# BusPirate-v4_ecard.net
KiCad netlist of a schematic drawn in EAGLE
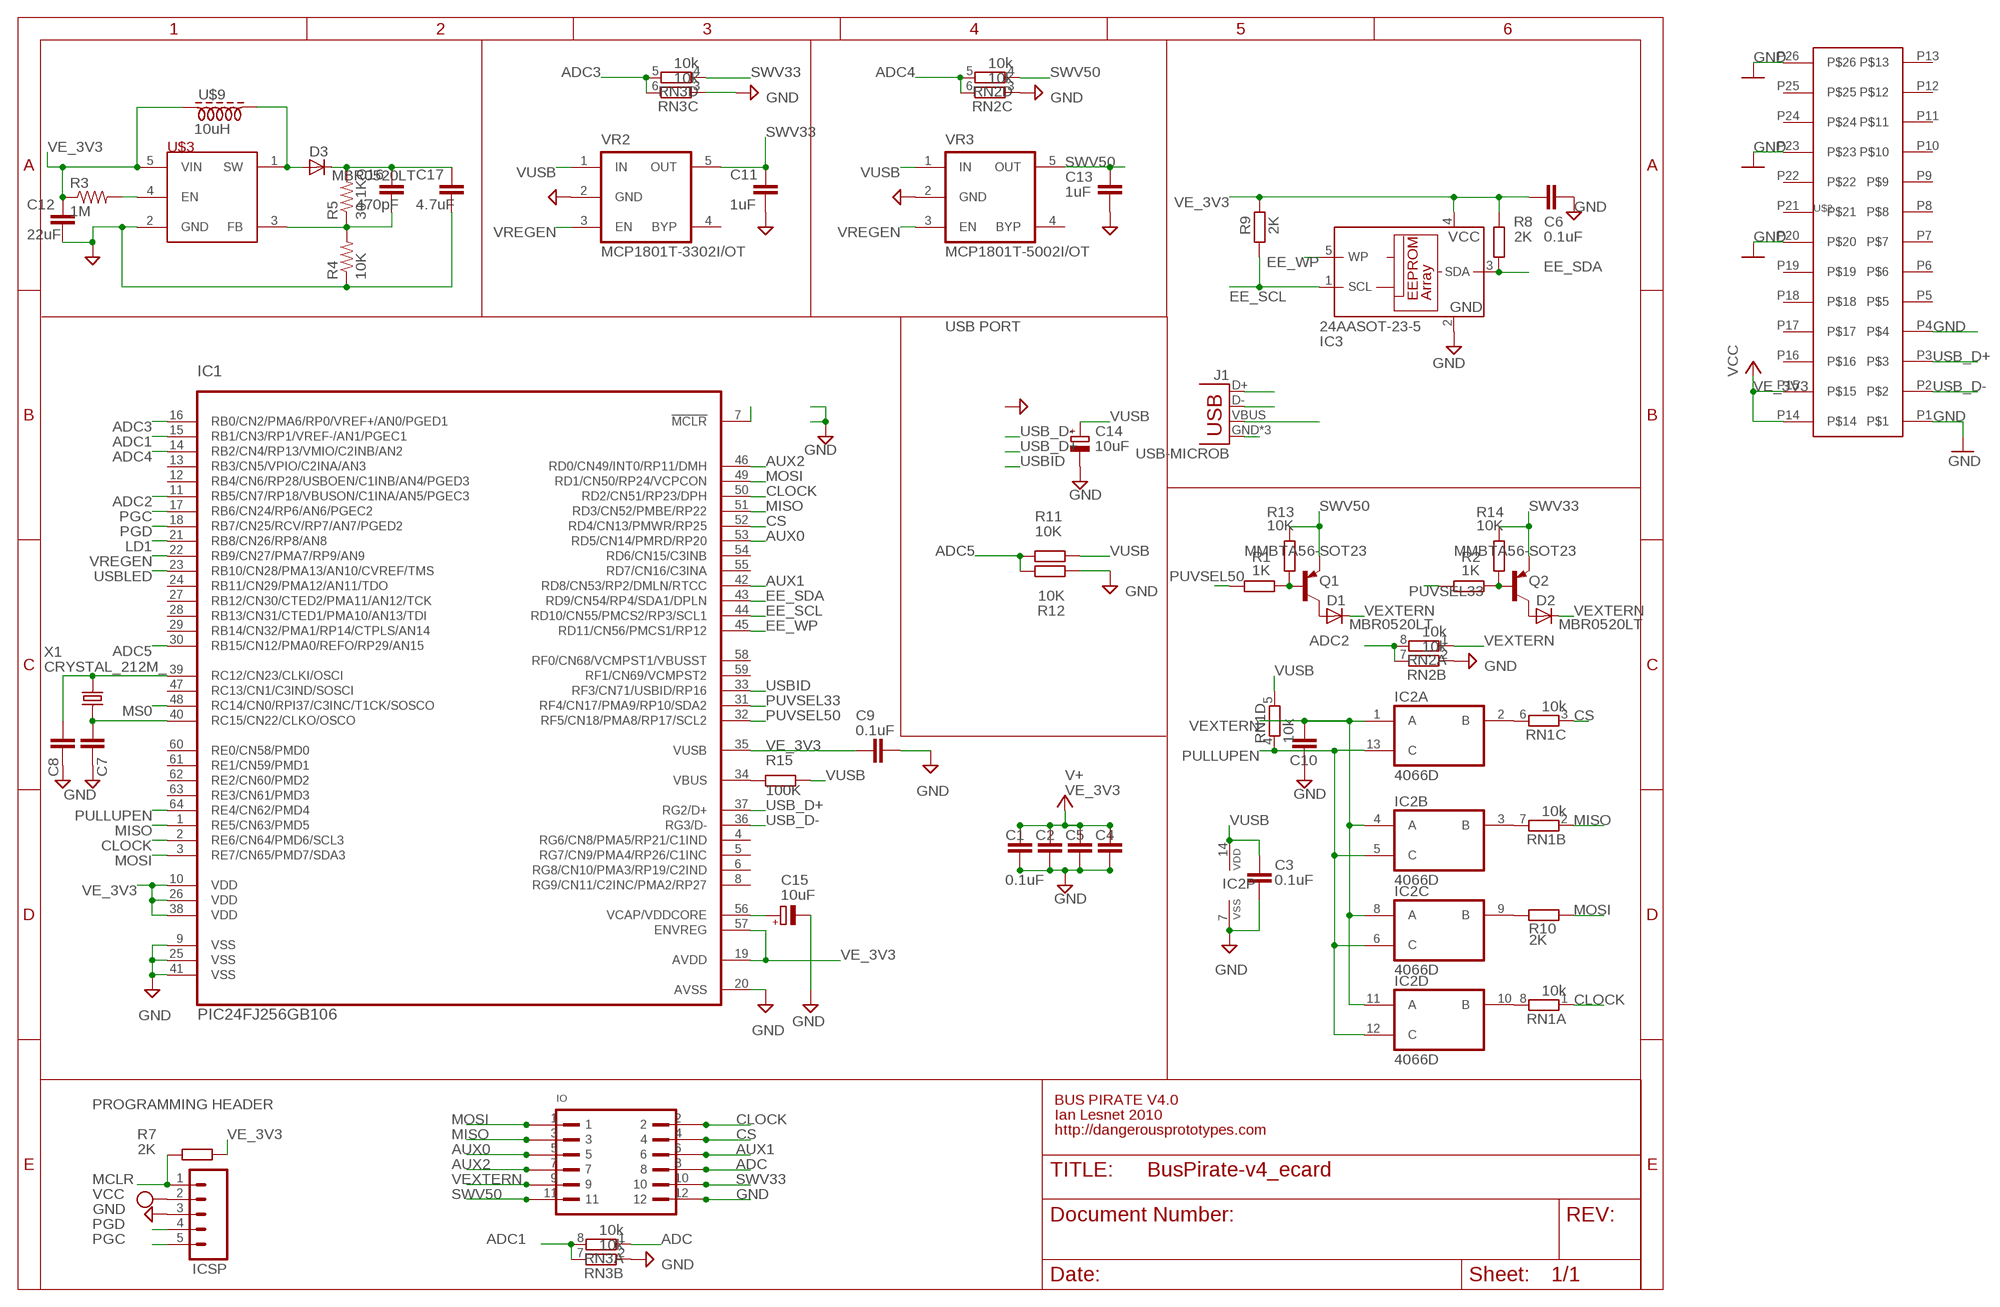
[diagram p0: schematic, sheet 1]

(export (version "E")
  (design (tool "Eeschema 10.0.6"))
  (components
    (comp (ref "C1")
      (value "0.1uF")
      (footprint "eagle-import:C0603")
      (libsource (lib "eagle-import") (part "C-EUC0603"))
    )
    (comp (ref "C2")
      (value "0.1uF")
      (footprint "eagle-import:C0603")
      (libsource (lib "eagle-import") (part "C-EUC0603"))
    )
    (comp (ref "C3")
      (value "0.1uF")
      (footprint "eagle-import:C0603")
      (libsource (lib "eagle-import") (part "C-EUC0603"))
    )
    (comp (ref "C4")
      (value "0.1uF")
      (footprint "eagle-import:C0603")
      (libsource (lib "eagle-import") (part "C-EUC0603"))
    )
    (comp (ref "C5")
      (value "0.1uF")
      (footprint "eagle-import:C0603")
      (libsource (lib "eagle-import") (part "C-EUC0603"))
    )
    (comp (ref "C6")
      (value "0.1uF")
      (footprint "eagle-import:C0603")
      (libsource (lib "eagle-import") (part "C-EUC0603"))
    )
    (comp (ref "C7")
      (value "27pF")
      (footprint "eagle-import:C0603")
      (libsource (lib "eagle-import") (part "C-EUC0603"))
    )
    (comp (ref "C8")
      (value "27pF")
      (footprint "eagle-import:C0603")
      (libsource (lib "eagle-import") (part "C-EUC0603"))
    )
    (comp (ref "C9")
      (value "0.1uF")
      (footprint "eagle-import:C0603")
      (libsource (lib "eagle-import") (part "C-EUC0603"))
    )
    (comp (ref "C10")
      (value "0.1uF")
      (footprint "eagle-import:C0603")
      (libsource (lib "eagle-import") (part "C-EUC0603"))
    )
    (comp (ref "C11")
      (value "1uF")
      (footprint "eagle-import:C0603")
      (libsource (lib "eagle-import") (part "C-EUC0603"))
    )
    (comp (ref "C12")
      (value "22uF")
      (footprint "eagle-import:C0603")
      (libsource (lib "eagle-import") (part "C-EUC0603"))
    )
    (comp (ref "C13")
      (value "1uF")
      (footprint "eagle-import:C0603")
      (libsource (lib "eagle-import") (part "C-EUC0603"))
    )
    (comp (ref "C14")
      (value "10uF")
      (footprint "eagle-import:SMC_A")
      (libsource (lib "eagle-import") (part "CPOL-EUSMCA"))
    )
    (comp (ref "C15")
      (value "10uF")
      (footprint "eagle-import:SMC_A")
      (libsource (lib "eagle-import") (part "CPOL-EUSMCA"))
    )
    (comp (ref "C16")
      (value "470pF")
      (footprint "eagle-import:C0603")
      (libsource (lib "eagle-import") (part "C-EUC0603"))
    )
    (comp (ref "C17")
      (value "4.7uF")
      (footprint "eagle-import:C0603")
      (libsource (lib "eagle-import") (part "C-EUC0603"))
    )
    (comp (ref "D1")
      (value "MBR0520LT")
      (footprint "eagle-import:SOD123")
      (libsource (lib "eagle-import") (part "MBR0520LT"))
    )
    (comp (ref "D2")
      (value "MBR0520LT")
      (footprint "eagle-import:SOD123")
      (libsource (lib "eagle-import") (part "MBR0520LT"))
    )
    (comp (ref "D3")
      (value "MBR0520LT")
      (footprint "eagle-import:SOD123")
      (libsource (lib "eagle-import") (part "MBR0520LT"))
    )
    (comp (ref "IC1")
      (value "PIC24FJ256GB106")
      (footprint "eagle-import:TQFP64-10X10")
      (libsource (lib "eagle-import") (part "PIC24FJ256GB106"))
    )
    (comp (ref "IC2")
      (value "4066D")
      (footprint "eagle-import:SO14")
      (libsource (lib "eagle-import") (part "4066D"))
    )
    (comp (ref "IC3")
      (value "24AASOT-23-5")
      (footprint "eagle-import:SOT-23-5")
      (libsource (lib "eagle-import") (part "24AA"))
    )
    (comp (ref "ICSP")
      (value "ICSP")
      (footprint "eagle-import:1X05")
      (libsource (lib "eagle-import") (part "M05"))
    )
    (comp (ref "IO")
      (value "PINSHRD-PTH-2X06")
      (footprint "eagle-import:PINSHRD_PTH_2X06")
      (libsource (lib "eagle-import") (part "PINSHRD-PTH-2X06"))
    )
    (comp (ref "J1")
      (value "USB-MICROB")
      (footprint "eagle-import:USB-MICROB")
      (libsource (lib "eagle-import") (part "USB-MICROB"))
    )
    (comp (ref "Q1")
      (value "MMBTA56-SOT23")
      (footprint "eagle-import:SOT23")
      (libsource (lib "eagle-import") (part "-?SOT23MMBTA56"))
    )
    (comp (ref "Q2")
      (value "MMBTA56-SOT23")
      (footprint "eagle-import:SOT23")
      (libsource (lib "eagle-import") (part "-?SOT23MMBTA56"))
    )
    (comp (ref "R1")
      (value "1K")
      (footprint "eagle-import:R0603")
      (libsource (lib "eagle-import") (part "R-EU_R0603"))
    )
    (comp (ref "R2")
      (value "1K")
      (footprint "eagle-import:R0603")
      (libsource (lib "eagle-import") (part "R-EU_R0603"))
    )
    (comp (ref "R3")
      (value "1M")
      (footprint "eagle-import:R0603")
      (libsource (lib "eagle-import") (part "R-US_R0603"))
    )
    (comp (ref "R4")
      (value "10K")
      (footprint "eagle-import:R0603")
      (libsource (lib "eagle-import") (part "R-US_R0603"))
    )
    (comp (ref "R5")
      (value "30.1K")
      (footprint "eagle-import:R0603")
      (libsource (lib "eagle-import") (part "R-US_R0603"))
    )
    (comp (ref "R7")
      (value "2K")
      (footprint "eagle-import:R0603")
      (libsource (lib "eagle-import") (part "R-EU_R0603"))
    )
    (comp (ref "R8")
      (value "2K")
      (footprint "eagle-import:R0603")
      (libsource (lib "eagle-import") (part "R-EU_R0603"))
    )
    (comp (ref "R9")
      (value "2K")
      (footprint "eagle-import:R0603")
      (libsource (lib "eagle-import") (part "R-EU_R0603"))
    )
    (comp (ref "R10")
      (value "2K")
      (footprint "eagle-import:R0603")
      (libsource (lib "eagle-import") (part "R-EU_R0603"))
    )
    (comp (ref "R11")
      (value "10K")
      (footprint "eagle-import:R0603")
      (libsource (lib "eagle-import") (part "resistor_R-EU_R0603"))
    )
    (comp (ref "R12")
      (value "10K")
      (footprint "eagle-import:R0603")
      (libsource (lib "eagle-import") (part "resistor_R-EU_R0603"))
    )
    (comp (ref "R13")
      (value "10K")
      (footprint "eagle-import:R0603")
      (libsource (lib "eagle-import") (part "R-EU_R0603"))
    )
    (comp (ref "R14")
      (value "10K")
      (footprint "eagle-import:R0603")
      (libsource (lib "eagle-import") (part "R-EU_R0603"))
    )
    (comp (ref "R15")
      (value "100K")
      (footprint "eagle-import:R0603")
      (libsource (lib "eagle-import") (part "R-EU_R0603"))
    )
    (comp (ref "RN1")
      (value "10k")
      (footprint "eagle-import:RN8P-4R-CRA06S")
      (libsource (lib "eagle-import") (part "RNETWORK"))
    )
    (comp (ref "RN2")
      (value "10k")
      (footprint "eagle-import:RN8P-4R-CRA06S")
      (libsource (lib "eagle-import") (part "RNETWORK"))
    )
    (comp (ref "RN3")
      (value "10k")
      (footprint "eagle-import:RN8P-4R-CRA06S")
      (libsource (lib "eagle-import") (part "RNETWORK"))
    )
    (comp (ref "U$2")
      (value "EXPRESSCARD")
      (footprint "eagle-import:EXPRESSCARD_EXPRESSCARD_PACK")
      (libsource (lib "eagle-import") (part "EXPRESSCARD"))
    )
    (comp (ref "U$3")
      (value "LMR62421")
      (footprint "eagle-import:SOT23-DBV")
      (libsource (lib "eagle-import") (part "LMR62421"))
    )
    (comp (ref "U$9")
      (value "10uH")
      (footprint "eagle-import:2520(1008)")
      (libsource (lib "eagle-import") (part "SMD_IND"))
    )
    (comp (ref "VR2")
      (value "MCP1801T-3302I/OT")
      (footprint "eagle-import:SOT-23-5")
      (libsource (lib "eagle-import") (part "MIC5205"))
    )
    (comp (ref "VR3")
      (value "MCP1801T-5002I/OT")
      (footprint "eagle-import:SOT-23-5")
      (libsource (lib "eagle-import") (part "MIC5205"))
    )
    (comp (ref "X1")
      (value "CRYSTAL_212M_")
      (footprint "eagle-import:4X6")
      (libsource (lib "eagle-import") (part "CRYSTAL_212M_"))
    )
  )
  (nets
    (net (code "1") (name "/ADC") (class "Default")
      (node (ref "IO") (pin "8") (pinfunction "8_8") (pintype "passive"))
      (node (ref "RN3") (pin "1") (pinfunction "1_1") (pintype "passive"))
    )
    (net (code "2") (name "/ADC1") (class "Default")
      (node (ref "IC1") (pin "15") (pinfunction "RB1/CN3/RP1/VREF-/AN1/PGEC1_15") (pintype "bidirectional"))
      (node (ref "RN3") (pin "7") (pinfunction "2_7") (pintype "passive"))
      (node (ref "RN3") (pin "8") (pinfunction "2_8") (pintype "passive"))
    )
    (net (code "3") (name "/ADC2") (class "Default")
      (node (ref "IC1") (pin "11") (pinfunction "RB5/CN7/RP18/VBUSON/C1INA/AN5/PGEC3_11") (pintype "bidirectional"))
      (node (ref "RN2") (pin "7") (pinfunction "2_7") (pintype "passive"))
      (node (ref "RN2") (pin "8") (pinfunction "2_8") (pintype "passive"))
    )
    (net (code "4") (name "/ADC3") (class "Default")
      (node (ref "IC1") (pin "16") (pinfunction "RB0/CN2/PMA6/RP0/VREF+/AN0/PGED1_16") (pintype "bidirectional"))
      (node (ref "RN3") (pin "5") (pinfunction "2_5") (pintype "passive"))
      (node (ref "RN3") (pin "6") (pinfunction "2_6") (pintype "passive"))
    )
    (net (code "5") (name "/ADC4") (class "Default")
      (node (ref "IC1") (pin "14") (pinfunction "RB2/CN4/RP13/VMIO/C2INB/AN2_14") (pintype "bidirectional"))
      (node (ref "RN2") (pin "5") (pinfunction "2_5") (pintype "passive"))
      (node (ref "RN2") (pin "6") (pinfunction "2_6") (pintype "passive"))
    )
    (net (code "6") (name "/ADC5") (class "Default")
      (node (ref "IC1") (pin "30") (pinfunction "RB15/CN12/PMA0/REFO/RP29/AN15_30") (pintype "bidirectional"))
      (node (ref "R11") (pin "2") (pinfunction "2_2") (pintype "passive"))
      (node (ref "R12") (pin "2") (pinfunction "2_2") (pintype "passive"))
    )
    (net (code "7") (name "/AUX0") (class "Default")
      (node (ref "IC1") (pin "53") (pinfunction "RD5/CN14/PMRD/RP20_53") (pintype "bidirectional"))
      (node (ref "IO") (pin "5") (pinfunction "5_5") (pintype "passive"))
    )
    (net (code "8") (name "/AUX1") (class "Default")
      (node (ref "IC1") (pin "42") (pinfunction "RD8/CN53/RP2/DMLN/RTCC_42") (pintype "bidirectional"))
      (node (ref "IO") (pin "6") (pinfunction "6_6") (pintype "passive"))
    )
    (net (code "9") (name "/AUX2") (class "Default")
      (node (ref "IC1") (pin "46") (pinfunction "RD0/CN49/INT0/RP11/DMH_46") (pintype "bidirectional"))
      (node (ref "IO") (pin "7") (pinfunction "7_7") (pintype "passive"))
    )
    (net (code "10") (name "/CLOCK") (class "Default")
      (node (ref "IC1") (pin "2") (pinfunction "RE6/CN64/PMD6/SCL3_2") (pintype "bidirectional"))
      (node (ref "IC1") (pin "50") (pinfunction "RD2/CN51/RP23/DPH_50") (pintype "bidirectional"))
      (node (ref "IO") (pin "2") (pinfunction "2_2") (pintype "passive"))
      (node (ref "RN1") (pin "1") (pinfunction "1_1") (pintype "passive"))
    )
    (net (code "11") (name "/CS") (class "Default")
      (node (ref "IC1") (pin "52") (pinfunction "RD4/CN13/PMWR/RP25_52") (pintype "bidirectional"))
      (node (ref "IO") (pin "4") (pinfunction "4_4") (pintype "passive"))
      (node (ref "RN1") (pin "3") (pinfunction "1_3") (pintype "passive"))
    )
    (net (code "12") (name "/EE_SCL") (class "Default")
      (node (ref "IC1") (pin "44") (pinfunction "RD10/CN55/PMCS2/RP3/SCL1_44") (pintype "bidirectional"))
      (node (ref "IC3") (pin "1") (pinfunction "SCL_1") (pintype "input"))
      (node (ref "R9") (pin "1") (pinfunction "1_1") (pintype "passive"))
    )
    (net (code "13") (name "/EE_SDA") (class "Default")
      (node (ref "IC1") (pin "43") (pinfunction "RD9/CN54/RP4/SDA1/DPLN_43") (pintype "bidirectional"))
      (node (ref "IC3") (pin "3") (pinfunction "SDA_3") (pintype "bidirectional"))
      (node (ref "R8") (pin "1") (pinfunction "1_1") (pintype "passive"))
    )
    (net (code "14") (name "/EE_WP") (class "Default")
      (node (ref "IC1") (pin "45") (pinfunction "RD11/CN56/PMCS1/RP12_45") (pintype "bidirectional"))
      (node (ref "IC3") (pin "5") (pinfunction "WP_5") (pintype "input"))
    )
    (net (code "15") (name "/LD1") (class "Default")
      (node (ref "IC1") (pin "21") (pinfunction "RB8/CN26/RP8/AN8_21") (pintype "bidirectional"))
    )
    (net (code "16") (name "/MCLR") (class "Default")
      (node (ref "IC1") (pin "7") (pinfunction "~{MCLR}_7") (pintype "input"))
      (node (ref "ICSP") (pin "1") (pinfunction "1_1") (pintype "passive"))
      (node (ref "R7") (pin "1") (pinfunction "1_1") (pintype "passive"))
    )
    (net (code "17") (name "/MISO") (class "Default")
      (node (ref "IC1") (pin "1") (pinfunction "RE5/CN63/PMD5_1") (pintype "bidirectional"))
      (node (ref "IC1") (pin "51") (pinfunction "RD3/CN52/PMBE/RP22_51") (pintype "bidirectional"))
      (node (ref "IO") (pin "3") (pinfunction "3_3") (pintype "passive"))
      (node (ref "RN1") (pin "2") (pinfunction "1_2") (pintype "passive"))
    )
    (net (code "18") (name "/MOSI") (class "Default")
      (node (ref "IC1") (pin "3") (pinfunction "RE7/CN65/PMD7/SDA3_3") (pintype "bidirectional"))
      (node (ref "IC1") (pin "49") (pinfunction "RD1/CN50/RP24/VCPCON_49") (pintype "bidirectional"))
      (node (ref "IO") (pin "1") (pinfunction "1_1") (pintype "passive"))
      (node (ref "R10") (pin "1") (pinfunction "1_1") (pintype "passive"))
    )
    (net (code "19") (name "/MS0") (class "Default")
      (node (ref "IC1") (pin "48") (pinfunction "RC14/CN0/RPI37/C3INC/T1CK/SOSCO_48") (pintype "bidirectional"))
    )
    (net (code "20") (name "/PGC") (class "Default")
      (node (ref "IC1") (pin "17") (pinfunction "RB6/CN24/RP6/AN6/PGEC2_17") (pintype "bidirectional"))
      (node (ref "ICSP") (pin "5") (pinfunction "5_5") (pintype "passive"))
    )
    (net (code "21") (name "/PGD") (class "Default")
      (node (ref "IC1") (pin "18") (pinfunction "RB7/CN25/RCV/RP7/AN7/PGED2_18") (pintype "bidirectional"))
      (node (ref "ICSP") (pin "4") (pinfunction "4_4") (pintype "passive"))
    )
    (net (code "22") (name "/PULLUPEN") (class "Default")
      (node (ref "IC1") (pin "64") (pinfunction "RE4/CN62/PMD4_64") (pintype "bidirectional"))
      (node (ref "IC2") (pin "12") (pinfunction "C_12") (pintype "input"))
      (node (ref "IC2") (pin "13") (pinfunction "C_13") (pintype "input"))
      (node (ref "IC2") (pin "5") (pinfunction "C_5") (pintype "input"))
      (node (ref "IC2") (pin "6") (pinfunction "C_6") (pintype "input"))
      (node (ref "RN1") (pin "4") (pinfunction "1_4") (pintype "passive"))
    )
    (net (code "23") (name "/PUVSEL33") (class "Default")
      (node (ref "IC1") (pin "31") (pinfunction "RF4/CN17/PMA9/RP10/SDA2_31") (pintype "bidirectional"))
      (node (ref "R2") (pin "2") (pinfunction "2_2") (pintype "passive"))
    )
    (net (code "24") (name "/PUVSEL50") (class "Default")
      (node (ref "IC1") (pin "32") (pinfunction "RF5/CN18/PMA8/RP17/SCL2_32") (pintype "bidirectional"))
      (node (ref "R1") (pin "2") (pinfunction "2_2") (pintype "passive"))
    )
    (net (code "25") (name "/SWV33") (class "Default")
      (node (ref "C11") (pin "1") (pinfunction "1_1") (pintype "passive"))
      (node (ref "IO") (pin "10") (pinfunction "10_10") (pintype "passive"))
      (node (ref "Q2") (pin "2") (pinfunction "E_2") (pintype "passive"))
      (node (ref "R14") (pin "1") (pinfunction "1_1") (pintype "passive"))
      (node (ref "RN3") (pin "4") (pinfunction "1_4") (pintype "passive"))
      (node (ref "VR2") (pin "5") (pinfunction "OUT_5") (pintype "bidirectional"))
    )
    (net (code "26") (name "/SWV50") (class "Default")
      (node (ref "C13") (pin "1") (pinfunction "1_1") (pintype "passive"))
      (node (ref "IO") (pin "11") (pinfunction "11_11") (pintype "passive"))
      (node (ref "Q1") (pin "2") (pinfunction "E_2") (pintype "passive"))
      (node (ref "R13") (pin "1") (pinfunction "1_1") (pintype "passive"))
      (node (ref "RN2") (pin "4") (pinfunction "1_4") (pintype "passive"))
      (node (ref "VR3") (pin "5") (pinfunction "OUT_5") (pintype "bidirectional"))
    )
    (net (code "27") (name "/USBID") (class "Default")
      (node (ref "IC1") (pin "33") (pinfunction "RF3/CN71/USBID/RP16_33") (pintype "bidirectional"))
    )
    (net (code "28") (name "/USBLED") (class "Default")
      (node (ref "IC1") (pin "23") (pinfunction "RB10/CN28/PMA13/AN10/CVREF/TMS_23") (pintype "bidirectional"))
    )
    (net (code "29") (name "/USB_D+") (class "Default")
      (node (ref "IC1") (pin "37") (pinfunction "RG2/D+_37") (pintype "bidirectional"))
      (node (ref "J1") (pin "D+") (pinfunction "D+_D+") (pintype "bidirectional"))
      (node (ref "U$2") (pin "P3") (pinfunction "P$3_P3") (pintype "bidirectional"))
    )
    (net (code "30") (name "/USB_D-") (class "Default")
      (node (ref "IC1") (pin "36") (pinfunction "RG3/D-_36") (pintype "bidirectional"))
      (node (ref "J1") (pin "D-") (pinfunction "D-_D-") (pintype "bidirectional"))
      (node (ref "U$2") (pin "P2") (pinfunction "P$2_P2") (pintype "bidirectional"))
    )
    (net (code "31") (name "/VEXTERN") (class "Default")
      (node (ref "C10") (pin "1") (pinfunction "1_1") (pintype "passive"))
      (node (ref "D1") (pin "C") (pinfunction "C_C") (pintype "passive"))
      (node (ref "D2") (pin "C") (pinfunction "C_C") (pintype "passive"))
      (node (ref "IC2") (pin "1") (pinfunction "A_1") (pintype "tri_state"))
      (node (ref "IC2") (pin "11") (pinfunction "A_11") (pintype "tri_state"))
      (node (ref "IC2") (pin "4") (pinfunction "A_4") (pintype "tri_state"))
      (node (ref "IC2") (pin "8") (pinfunction "A_8") (pintype "tri_state"))
      (node (ref "IO") (pin "9") (pinfunction "9_9") (pintype "passive"))
      (node (ref "RN2") (pin "1") (pinfunction "1_1") (pintype "passive"))
    )
    (net (code "32") (name "/VREGEN") (class "Default")
      (node (ref "IC1") (pin "22") (pinfunction "RB9/CN27/PMA7/RP9/AN9_22") (pintype "bidirectional"))
      (node (ref "VR2") (pin "3") (pinfunction "EN_3") (pintype "bidirectional"))
      (node (ref "VR3") (pin "3") (pinfunction "EN_3") (pintype "bidirectional"))
    )
    (net (code "33") (name "/VUSB") (class "Default")
      (node (ref "C14") (pin "+") (pinfunction "+_+") (pintype "passive"))
      (node (ref "C16") (pin "1") (pinfunction "1_1") (pintype "passive"))
      (node (ref "C17") (pin "1") (pinfunction "1_1") (pintype "passive"))
      (node (ref "C3") (pin "1") (pinfunction "1_1") (pintype "passive"))
      (node (ref "D3") (pin "C") (pinfunction "C_C") (pintype "passive"))
      (node (ref "IC2") (pin "14") (pinfunction "VDD_14") (pintype "power_in"))
      (node (ref "J1") (pin "VBUS") (pinfunction "VBUS_VBUS") (pintype "bidirectional"))
      (node (ref "R11") (pin "1") (pinfunction "1_1") (pintype "passive"))
      (node (ref "R15") (pin "1") (pinfunction "1_1") (pintype "passive"))
      (node (ref "R5") (pin "2") (pinfunction "2_2") (pintype "passive"))
      (node (ref "RN1") (pin "5") (pinfunction "2_5") (pintype "passive"))
      (node (ref "VR2") (pin "1") (pinfunction "IN_1") (pintype "bidirectional"))
      (node (ref "VR3") (pin "1") (pinfunction "IN_1") (pintype "bidirectional"))
    )
    (net (code "34") (name "GND") (class "Default")
      (node (ref "C1") (pin "2") (pinfunction "2_2") (pintype "passive"))
      (node (ref "C10") (pin "2") (pinfunction "2_2") (pintype "passive"))
      (node (ref "C11") (pin "2") (pinfunction "2_2") (pintype "passive"))
      (node (ref "C12") (pin "2") (pinfunction "2_2") (pintype "passive"))
      (node (ref "C13") (pin "2") (pinfunction "2_2") (pintype "passive"))
      (node (ref "C14") (pin "-") (pinfunction "-_-") (pintype "passive"))
      (node (ref "C15") (pin "-") (pinfunction "-_-") (pintype "passive"))
      (node (ref "C17") (pin "2") (pinfunction "2_2") (pintype "passive"))
      (node (ref "C2") (pin "2") (pinfunction "2_2") (pintype "passive"))
      (node (ref "C3") (pin "2") (pinfunction "2_2") (pintype "passive"))
      (node (ref "C4") (pin "2") (pinfunction "2_2") (pintype "passive"))
      (node (ref "C5") (pin "2") (pinfunction "2_2") (pintype "passive"))
      (node (ref "C6") (pin "2") (pinfunction "2_2") (pintype "passive"))
      (node (ref "C7") (pin "2") (pinfunction "2_2") (pintype "passive"))
      (node (ref "C8") (pin "2") (pinfunction "2_2") (pintype "passive"))
      (node (ref "C9") (pin "2") (pinfunction "2_2") (pintype "passive"))
      (node (ref "IC1") (pin "20") (pinfunction "AVSS_20") (pintype "power_in"))
      (node (ref "IC1") (pin "25") (pinfunction "VSS_25") (pintype "power_in"))
      (node (ref "IC1") (pin "41") (pinfunction "VSS_41") (pintype "power_in"))
      (node (ref "IC1") (pin "9") (pinfunction "VSS_9") (pintype "power_in"))
      (node (ref "IC2") (pin "7") (pinfunction "VSS_7") (pintype "power_in"))
      (node (ref "IC3") (pin "2") (pinfunction "GND_2") (pintype "power_in"))
      (node (ref "ICSP") (pin "3") (pinfunction "3_3") (pintype "passive"))
      (node (ref "IO") (pin "12") (pinfunction "12_12") (pintype "passive"))
      (node (ref "J1") (pin "GND") (pinfunction "GND_GND") (pintype "bidirectional"))
      (node (ref "J1") (pin "MT1") (pinfunction "GND_MT1") (pintype "bidirectional"))
      (node (ref "J1") (pin "MT2") (pinfunction "GND_MT2") (pintype "bidirectional"))
      (node (ref "R12") (pin "1") (pinfunction "1_1") (pintype "passive"))
      (node (ref "R4") (pin "1") (pinfunction "1_1") (pintype "passive"))
      (node (ref "RN2") (pin "2") (pinfunction "1_2") (pintype "passive"))
      (node (ref "RN2") (pin "3") (pinfunction "1_3") (pintype "passive"))
      (node (ref "RN3") (pin "2") (pinfunction "1_2") (pintype "passive"))
      (node (ref "RN3") (pin "3") (pinfunction "1_3") (pintype "passive"))
      (node (ref "U$2") (pin "P1") (pinfunction "P$1_P1") (pintype "bidirectional"))
      (node (ref "U$2") (pin "P20") (pinfunction "P$20_P20") (pintype "bidirectional"))
      (node (ref "U$2") (pin "P23") (pinfunction "P$23_P23") (pintype "bidirectional"))
      (node (ref "U$2") (pin "P26") (pinfunction "P$26_P26") (pintype "bidirectional"))
      (node (ref "U$2") (pin "P4") (pinfunction "P$4_P4") (pintype "bidirectional"))
      (node (ref "U$3") (pin "2") (pinfunction "GND_2") (pintype "bidirectional"))
      (node (ref "VR2") (pin "2") (pinfunction "GND_2") (pintype "bidirectional"))
      (node (ref "VR3") (pin "2") (pinfunction "GND_2") (pintype "bidirectional"))
    )
    (net (code "35") (name "Net-(IC1-RC12{slash}CN23{slash}CLKI{slash}OSCI)") (class "Default")
      (node (ref "C8") (pin "1") (pinfunction "1_1") (pintype "passive"))
      (node (ref "IC1") (pin "39") (pinfunction "RC12/CN23/CLKI/OSCI_39") (pintype "bidirectional"))
      (node (ref "X1") (pin "1") (pinfunction "X1_1") (pintype "bidirectional"))
    )
    (net (code "36") (name "Net-(IC1-RC15{slash}CN22{slash}CLKO{slash}OSCO)") (class "Default")
      (node (ref "C7") (pin "1") (pinfunction "1_1") (pintype "passive"))
      (node (ref "IC1") (pin "40") (pinfunction "RC15/CN22/CLKO/OSCO_40") (pintype "bidirectional"))
      (node (ref "X1") (pin "2") (pinfunction "X2_2") (pintype "bidirectional"))
    )
    (net (code "37") (name "Net-(IC1-VBUS)") (class "Default")
      (node (ref "IC1") (pin "34") (pinfunction "VBUS_34") (pintype "bidirectional"))
      (node (ref "R15") (pin "2") (pinfunction "2_2") (pintype "passive"))
    )
    (net (code "38") (name "Net-(IC1-VCAP{slash}VDDCORE)") (class "Default")
      (node (ref "C15") (pin "+") (pinfunction "+_+") (pintype "passive"))
      (node (ref "IC1") (pin "56") (pinfunction "VCAP/VDDCORE_56") (pintype "bidirectional"))
    )
    (net (code "39") (name "Net-(IC2A-B)") (class "Default")
      (node (ref "IC2") (pin "2") (pinfunction "B_2") (pintype "tri_state"))
      (node (ref "RN1") (pin "6") (pinfunction "2_6") (pintype "passive"))
    )
    (net (code "40") (name "Net-(IC2B-B)") (class "Default")
      (node (ref "IC2") (pin "3") (pinfunction "B_3") (pintype "tri_state"))
      (node (ref "RN1") (pin "7") (pinfunction "2_7") (pintype "passive"))
    )
    (net (code "41") (name "Net-(IC2C-B)") (class "Default")
      (node (ref "IC2") (pin "9") (pinfunction "B_9") (pintype "tri_state"))
      (node (ref "R10") (pin "2") (pinfunction "2_2") (pintype "passive"))
    )
    (net (code "42") (name "Net-(IC2D-B)") (class "Default")
      (node (ref "IC2") (pin "10") (pinfunction "B_10") (pintype "tri_state"))
      (node (ref "RN1") (pin "8") (pinfunction "2_8") (pintype "passive"))
    )
    (net (code "43") (name "Net-(Q1-B)") (class "Default")
      (node (ref "Q1") (pin "1") (pinfunction "B_1") (pintype "passive"))
      (node (ref "R1") (pin "1") (pinfunction "1_1") (pintype "passive"))
      (node (ref "R13") (pin "2") (pinfunction "2_2") (pintype "passive"))
    )
    (net (code "44") (name "Net-(Q1-C)") (class "Default")
      (node (ref "D1") (pin "A") (pinfunction "A_A") (pintype "passive"))
      (node (ref "Q1") (pin "3") (pinfunction "C_3") (pintype "passive"))
    )
    (net (code "45") (name "Net-(Q2-B)") (class "Default")
      (node (ref "Q2") (pin "1") (pinfunction "B_1") (pintype "passive"))
      (node (ref "R14") (pin "2") (pinfunction "2_2") (pintype "passive"))
      (node (ref "R2") (pin "1") (pinfunction "1_1") (pintype "passive"))
    )
    (net (code "46") (name "Net-(Q2-C)") (class "Default")
      (node (ref "D2") (pin "A") (pinfunction "A_A") (pintype "passive"))
      (node (ref "Q2") (pin "3") (pinfunction "C_3") (pintype "passive"))
    )
    (net (code "47") (name "Net-(U$3-EN)") (class "Default")
      (node (ref "R3") (pin "2") (pinfunction "2_2") (pintype "passive"))
      (node (ref "U$3") (pin "4") (pinfunction "EN_4") (pintype "bidirectional"))
    )
    (net (code "48") (name "Net-(U$3-FB)") (class "Default")
      (node (ref "C16") (pin "2") (pinfunction "2_2") (pintype "passive"))
      (node (ref "R4") (pin "2") (pinfunction "2_2") (pintype "passive"))
      (node (ref "R5") (pin "1") (pinfunction "1_1") (pintype "passive"))
      (node (ref "U$3") (pin "3") (pinfunction "FB_3") (pintype "bidirectional"))
    )
    (net (code "49") (name "Net-(U$3-SW)") (class "Default")
      (node (ref "D3") (pin "A") (pinfunction "A_A") (pintype "passive"))
      (node (ref "U$3") (pin "1") (pinfunction "SW_1") (pintype "bidirectional"))
      (node (ref "U$9") (pin "2") (pinfunction "2_2") (pintype "passive"))
    )
    (net (code "50") (name "V+") (class "Default")
      (node (ref "C1") (pin "1") (pinfunction "1_1") (pintype "passive"))
      (node (ref "C12") (pin "1") (pinfunction "1_1") (pintype "passive"))
      (node (ref "C2") (pin "1") (pinfunction "1_1") (pintype "passive"))
      (node (ref "C4") (pin "1") (pinfunction "1_1") (pintype "passive"))
      (node (ref "C5") (pin "1") (pinfunction "1_1") (pintype "passive"))
      (node (ref "C6") (pin "1") (pinfunction "1_1") (pintype "passive"))
      (node (ref "C9") (pin "1") (pinfunction "1_1") (pintype "passive"))
      (node (ref "IC1") (pin "10") (pinfunction "VDD_10") (pintype "power_in"))
      (node (ref "IC1") (pin "19") (pinfunction "AVDD_19") (pintype "power_in"))
      (node (ref "IC1") (pin "26") (pinfunction "VDD_26") (pintype "power_in"))
      (node (ref "IC1") (pin "35") (pinfunction "VUSB_35") (pintype "bidirectional"))
      (node (ref "IC1") (pin "38") (pinfunction "VDD_38") (pintype "power_in"))
      (node (ref "IC1") (pin "57") (pinfunction "ENVREG_57") (pintype "bidirectional"))
      (node (ref "IC3") (pin "4") (pinfunction "VCC_4") (pintype "power_in"))
      (node (ref "ICSP") (pin "2") (pinfunction "2_2") (pintype "passive"))
      (node (ref "R3") (pin "1") (pinfunction "1_1") (pintype "passive"))
      (node (ref "R7") (pin "2") (pinfunction "2_2") (pintype "passive"))
      (node (ref "R8") (pin "2") (pinfunction "2_2") (pintype "passive"))
      (node (ref "R9") (pin "2") (pinfunction "2_2") (pintype "passive"))
      (node (ref "U$2") (pin "P14") (pinfunction "P$14_P14") (pintype "bidirectional"))
      (node (ref "U$2") (pin "P15") (pinfunction "P$15_P15") (pintype "bidirectional"))
      (node (ref "U$3") (pin "5") (pinfunction "VIN_5") (pintype "bidirectional"))
      (node (ref "U$9") (pin "1") (pinfunction "1_1") (pintype "passive"))
    )
    (net (code "51") (name "unconnected-(IC1-RB3{slash}CN5{slash}VPIO{slash}C2INA{slash}AN3-Pad13)") (class "Default")
      (node (ref "IC1") (pin "13") (pinfunction "RB3/CN5/VPIO/C2INA/AN3_13") (pintype "bidirectional"))
    )
    (net (code "52") (name "unconnected-(IC1-RB4{slash}CN6{slash}RP28{slash}USBOEN{slash}C1INB{slash}AN4{slash}PGED3-Pad12)") (class "Default")
      (node (ref "IC1") (pin "12") (pinfunction "RB4/CN6/RP28/USBOEN/C1INB/AN4/PGED3_12") (pintype "bidirectional"))
    )
    (net (code "53") (name "unconnected-(IC1-RB11{slash}CN29{slash}PMA12{slash}AN11{slash}TDO-Pad24)") (class "Default")
      (node (ref "IC1") (pin "24") (pinfunction "RB11/CN29/PMA12/AN11/TDO_24") (pintype "bidirectional"))
    )
    (net (code "54") (name "unconnected-(IC1-RB12{slash}CN30{slash}CTED2{slash}PMA11{slash}AN12{slash}TCK-Pad27)") (class "Default")
      (node (ref "IC1") (pin "27") (pinfunction "RB12/CN30/CTED2/PMA11/AN12/TCK_27") (pintype "bidirectional"))
    )
    (net (code "55") (name "unconnected-(IC1-RB13{slash}CN31{slash}CTED1{slash}PMA10{slash}AN13{slash}TDI-Pad28)") (class "Default")
      (node (ref "IC1") (pin "28") (pinfunction "RB13/CN31/CTED1/PMA10/AN13/TDI_28") (pintype "bidirectional"))
    )
    (net (code "56") (name "unconnected-(IC1-RB14{slash}CN32{slash}PMA1{slash}RP14{slash}CTPLS{slash}AN14-Pad29)") (class "Default")
      (node (ref "IC1") (pin "29") (pinfunction "RB14/CN32/PMA1/RP14/CTPLS/AN14_29") (pintype "bidirectional"))
    )
    (net (code "57") (name "unconnected-(IC1-RC13{slash}CN1{slash}C3IND{slash}SOSCI-Pad47)") (class "Default")
      (node (ref "IC1") (pin "47") (pinfunction "RC13/CN1/C3IND/SOSCI_47") (pintype "bidirectional"))
    )
    (net (code "58") (name "unconnected-(IC1-RD6{slash}CN15{slash}C3INB-Pad54)") (class "Default")
      (node (ref "IC1") (pin "54") (pinfunction "RD6/CN15/C3INB_54") (pintype "bidirectional"))
    )
    (net (code "59") (name "unconnected-(IC1-RD7{slash}CN16{slash}C3INA-Pad55)") (class "Default")
      (node (ref "IC1") (pin "55") (pinfunction "RD7/CN16/C3INA_55") (pintype "bidirectional"))
    )
    (net (code "60") (name "unconnected-(IC1-RE0{slash}CN58{slash}PMD0-Pad60)") (class "Default")
      (node (ref "IC1") (pin "60") (pinfunction "RE0/CN58/PMD0_60") (pintype "bidirectional"))
    )
    (net (code "61") (name "unconnected-(IC1-RE1{slash}CN59{slash}PMD1-Pad61)") (class "Default")
      (node (ref "IC1") (pin "61") (pinfunction "RE1/CN59/PMD1_61") (pintype "bidirectional"))
    )
    (net (code "62") (name "unconnected-(IC1-RE2{slash}CN60{slash}PMD2-Pad62)") (class "Default")
      (node (ref "IC1") (pin "62") (pinfunction "RE2/CN60/PMD2_62") (pintype "bidirectional"))
    )
    (net (code "63") (name "unconnected-(IC1-RE3{slash}CN61{slash}PMD3-Pad63)") (class "Default")
      (node (ref "IC1") (pin "63") (pinfunction "RE3/CN61/PMD3_63") (pintype "bidirectional"))
    )
    (net (code "64") (name "unconnected-(IC1-RF0{slash}CN68{slash}VCMPST1{slash}VBUSST-Pad58)") (class "Default")
      (node (ref "IC1") (pin "58") (pinfunction "RF0/CN68/VCMPST1/VBUSST_58") (pintype "bidirectional"))
    )
    (net (code "65") (name "unconnected-(IC1-RF1{slash}CN69{slash}VCMPST2-Pad59)") (class "Default")
      (node (ref "IC1") (pin "59") (pinfunction "RF1/CN69/VCMPST2_59") (pintype "bidirectional"))
    )
    (net (code "66") (name "unconnected-(IC1-RG6{slash}CN8{slash}PMA5{slash}RP21{slash}C1IND-Pad4)") (class "Default")
      (node (ref "IC1") (pin "4") (pinfunction "RG6/CN8/PMA5/RP21/C1IND_4") (pintype "bidirectional"))
    )
    (net (code "67") (name "unconnected-(IC1-RG7{slash}CN9{slash}PMA4{slash}RP26{slash}C1INC-Pad5)") (class "Default")
      (node (ref "IC1") (pin "5") (pinfunction "RG7/CN9/PMA4/RP26/C1INC_5") (pintype "bidirectional"))
    )
    (net (code "68") (name "unconnected-(IC1-RG8{slash}CN10{slash}PMA3{slash}RP19{slash}C2IND-Pad6)") (class "Default")
      (node (ref "IC1") (pin "6") (pinfunction "RG8/CN10/PMA3/RP19/C2IND_6") (pintype "bidirectional"))
    )
    (net (code "69") (name "unconnected-(IC1-RG9{slash}CN11{slash}C2INC{slash}PMA2{slash}RP27-Pad8)") (class "Default")
      (node (ref "IC1") (pin "8") (pinfunction "RG9/CN11/C2INC/PMA2/RP27_8") (pintype "bidirectional"))
    )
    (net (code "70") (name "unconnected-(U$2-P$5-PadP5)") (class "Default")
      (node (ref "U$2") (pin "P5") (pinfunction "P$5_P5") (pintype "bidirectional"))
    )
    (net (code "71") (name "unconnected-(U$2-P$6-PadP6)") (class "Default")
      (node (ref "U$2") (pin "P6") (pinfunction "P$6_P6") (pintype "bidirectional"))
    )
    (net (code "72") (name "unconnected-(U$2-P$7-PadP7)") (class "Default")
      (node (ref "U$2") (pin "P7") (pinfunction "P$7_P7") (pintype "bidirectional"))
    )
    (net (code "73") (name "unconnected-(U$2-P$8-PadP8)") (class "Default")
      (node (ref "U$2") (pin "P8") (pinfunction "P$8_P8") (pintype "bidirectional"))
    )
    (net (code "74") (name "unconnected-(U$2-P$9-PadP9)") (class "Default")
      (node (ref "U$2") (pin "P9") (pinfunction "P$9_P9") (pintype "bidirectional"))
    )
    (net (code "75") (name "unconnected-(U$2-P$10-PadP10)") (class "Default")
      (node (ref "U$2") (pin "P10") (pinfunction "P$10_P10") (pintype "bidirectional"))
    )
    (net (code "76") (name "unconnected-(U$2-P$11-PadP11)") (class "Default")
      (node (ref "U$2") (pin "P11") (pinfunction "P$11_P11") (pintype "bidirectional"))
    )
    (net (code "77") (name "unconnected-(U$2-P$12-PadP12)") (class "Default")
      (node (ref "U$2") (pin "P12") (pinfunction "P$12_P12") (pintype "bidirectional"))
    )
    (net (code "78") (name "unconnected-(U$2-P$13-PadP13)") (class "Default")
      (node (ref "U$2") (pin "P13") (pinfunction "P$13_P13") (pintype "bidirectional"))
    )
    (net (code "79") (name "unconnected-(U$2-P$16-PadP16)") (class "Default")
      (node (ref "U$2") (pin "P16") (pinfunction "P$16_P16") (pintype "bidirectional"))
    )
    (net (code "80") (name "unconnected-(U$2-P$17-PadP17)") (class "Default")
      (node (ref "U$2") (pin "P17") (pinfunction "P$17_P17") (pintype "bidirectional"))
    )
    (net (code "81") (name "unconnected-(U$2-P$18-PadP18)") (class "Default")
      (node (ref "U$2") (pin "P18") (pinfunction "P$18_P18") (pintype "bidirectional"))
    )
    (net (code "82") (name "unconnected-(U$2-P$19-PadP19)") (class "Default")
      (node (ref "U$2") (pin "P19") (pinfunction "P$19_P19") (pintype "bidirectional"))
    )
    (net (code "83") (name "unconnected-(U$2-P$21-PadP21)") (class "Default")
      (node (ref "U$2") (pin "P21") (pinfunction "P$21_P21") (pintype "bidirectional"))
    )
    (net (code "84") (name "unconnected-(U$2-P$22-PadP22)") (class "Default")
      (node (ref "U$2") (pin "P22") (pinfunction "P$22_P22") (pintype "bidirectional"))
    )
    (net (code "85") (name "unconnected-(U$2-P$24-PadP24)") (class "Default")
      (node (ref "U$2") (pin "P24") (pinfunction "P$24_P24") (pintype "bidirectional"))
    )
    (net (code "86") (name "unconnected-(U$2-P$25-PadP25)") (class "Default")
      (node (ref "U$2") (pin "P25") (pinfunction "P$25_P25") (pintype "bidirectional"))
    )
    (net (code "87") (name "unconnected-(VR2-BYP-Pad4)") (class "Default")
      (node (ref "VR2") (pin "4") (pinfunction "BYP_4") (pintype "bidirectional"))
    )
    (net (code "88") (name "unconnected-(VR3-BYP-Pad4)") (class "Default")
      (node (ref "VR3") (pin "4") (pinfunction "BYP_4") (pintype "bidirectional"))
    )
  )
)
